# relay.net
KiCad netlist of a schematic drawn in EAGLE
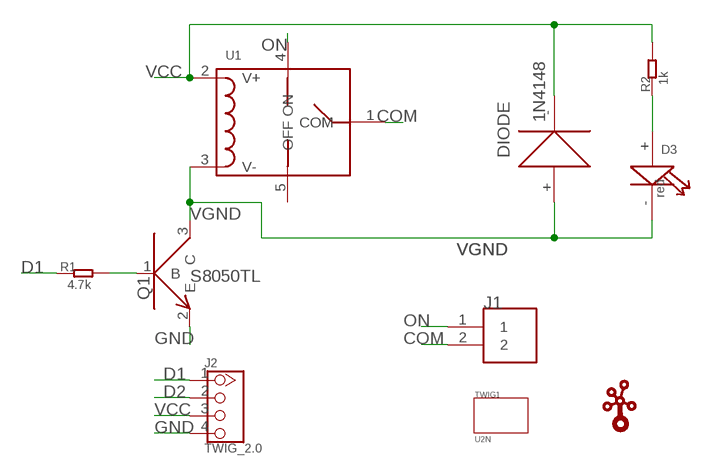
[diagram p0: schematic, sheet 1]

(export (version "E")
  (design (tool "Eeschema 10.0.6"))
  (components
    (comp (ref "D3")
      (value "red")
      (footprint "eagle-import:LED0805")
      (libsource (lib "eagle-import") (part "LED0805"))
    )
    (comp (ref "DIODE")
      (value "1N4148")
      (footprint "eagle-import:DIODE1206")
      (libsource (lib "eagle-import") (part "DIODE1206"))
    )
    (comp (ref "J1")
      (value "CON2")
      (footprint "eagle-import:CON2")
      (libsource (lib "eagle-import") (part "CON2"))
    )
    (comp (ref "J2")
      (value "TWIG_2.0")
      (footprint "eagle-import:2.0_1X4")
      (libsource (lib "eagle-import") (part "TWIG_2.0"))
    )
    (comp (ref "Q1")
      (value "NPN_9013")
      (footprint "eagle-import:SOT23")
      (libsource (lib "eagle-import") (part "NPN_9013"))
    )
    (comp (ref "R1")
      (value "4.7k")
      (footprint "eagle-import:0603")
      (libsource (lib "eagle-import") (part "R0603"))
    )
    (comp (ref "R2")
      (value "1k")
      (footprint "eagle-import:0603")
      (libsource (lib "eagle-import") (part "R0603"))
    )
    (comp (ref "TWIG1")
      (value "U2N")
      (footprint "eagle-import:U2N")
      (libsource (lib "eagle-import") (part "U2N"))
    )
    (comp (ref "U$1")
      (value "TWIGLOGOTWIGLOGO_SMALL")
      (footprint "eagle-import:TWIGLOGO_SMALL")
      (libsource (lib "eagle-import") (part "TWIGLOGOTWIGLOGO_SMALL"))
    )
    (comp (ref "U1")
      (value "RELAY")
      (footprint "eagle-import:RELAY")
      (libsource (lib "eagle-import") (part "RELAY"))
    )
  )
  (nets
    (net (code "1") (name "/COM") (class "Default")
      (node (ref "J1") (pin "2") (pinfunction "2_2") (pintype "bidirectional"))
      (node (ref "U1") (pin "1") (pinfunction "COM_1") (pintype "bidirectional"))
    )
    (net (code "2") (name "/D1") (class "Default")
      (node (ref "J2") (pin "1") (pinfunction "1_1") (pintype "bidirectional"))
      (node (ref "R1") (pin "1") (pinfunction "1_1") (pintype "bidirectional"))
    )
    (net (code "3") (name "/D2") (class "Default")
      (node (ref "J2") (pin "2") (pinfunction "2_2") (pintype "bidirectional"))
    )
    (net (code "4") (name "/GND") (class "Default")
      (node (ref "J2") (pin "4") (pinfunction "4_4") (pintype "bidirectional"))
      (node (ref "Q1") (pin "2") (pinfunction "E_2") (pintype "bidirectional"))
    )
    (net (code "5") (name "/ON") (class "Default")
      (node (ref "J1") (pin "1") (pinfunction "1_1") (pintype "bidirectional"))
      (node (ref "U1") (pin "4") (pinfunction "ON_4") (pintype "bidirectional"))
    )
    (net (code "6") (name "/VCC") (class "Default")
      (node (ref "DIODE") (pin "-") (pinfunction "P$2_-") (pintype "bidirectional"))
      (node (ref "J2") (pin "3") (pinfunction "3_3") (pintype "bidirectional"))
      (node (ref "R2") (pin "2") (pinfunction "2_2") (pintype "bidirectional"))
      (node (ref "U1") (pin "2") (pinfunction "V+_2") (pintype "bidirectional"))
    )
    (net (code "7") (name "/VGND") (class "Default")
      (node (ref "D3") (pin "-") (pinfunction "-_-") (pintype "bidirectional"))
      (node (ref "DIODE") (pin "+") (pinfunction "P$1_+") (pintype "bidirectional"))
      (node (ref "Q1") (pin "3") (pinfunction "C_3") (pintype "bidirectional"))
      (node (ref "U1") (pin "3") (pinfunction "V-_3") (pintype "bidirectional"))
    )
    (net (code "8") (name "Net-(D3-Pad+)") (class "Default")
      (node (ref "D3") (pin "+") (pinfunction "+_+") (pintype "bidirectional"))
      (node (ref "R2") (pin "1") (pinfunction "1_1") (pintype "bidirectional"))
    )
    (net (code "9") (name "Net-(Q1-B)") (class "Default")
      (node (ref "Q1") (pin "1") (pinfunction "B_1") (pintype "bidirectional"))
      (node (ref "R1") (pin "2") (pinfunction "2_2") (pintype "bidirectional"))
    )
    (net (code "10") (name "unconnected-(U1-OFF-Pad5)") (class "Default")
      (node (ref "U1") (pin "5") (pinfunction "OFF_5") (pintype "bidirectional"))
    )
  )
)
